# ATmega128RFA1-DevBoard-unplaced.net
KiCad netlist of a schematic drawn in EAGLE
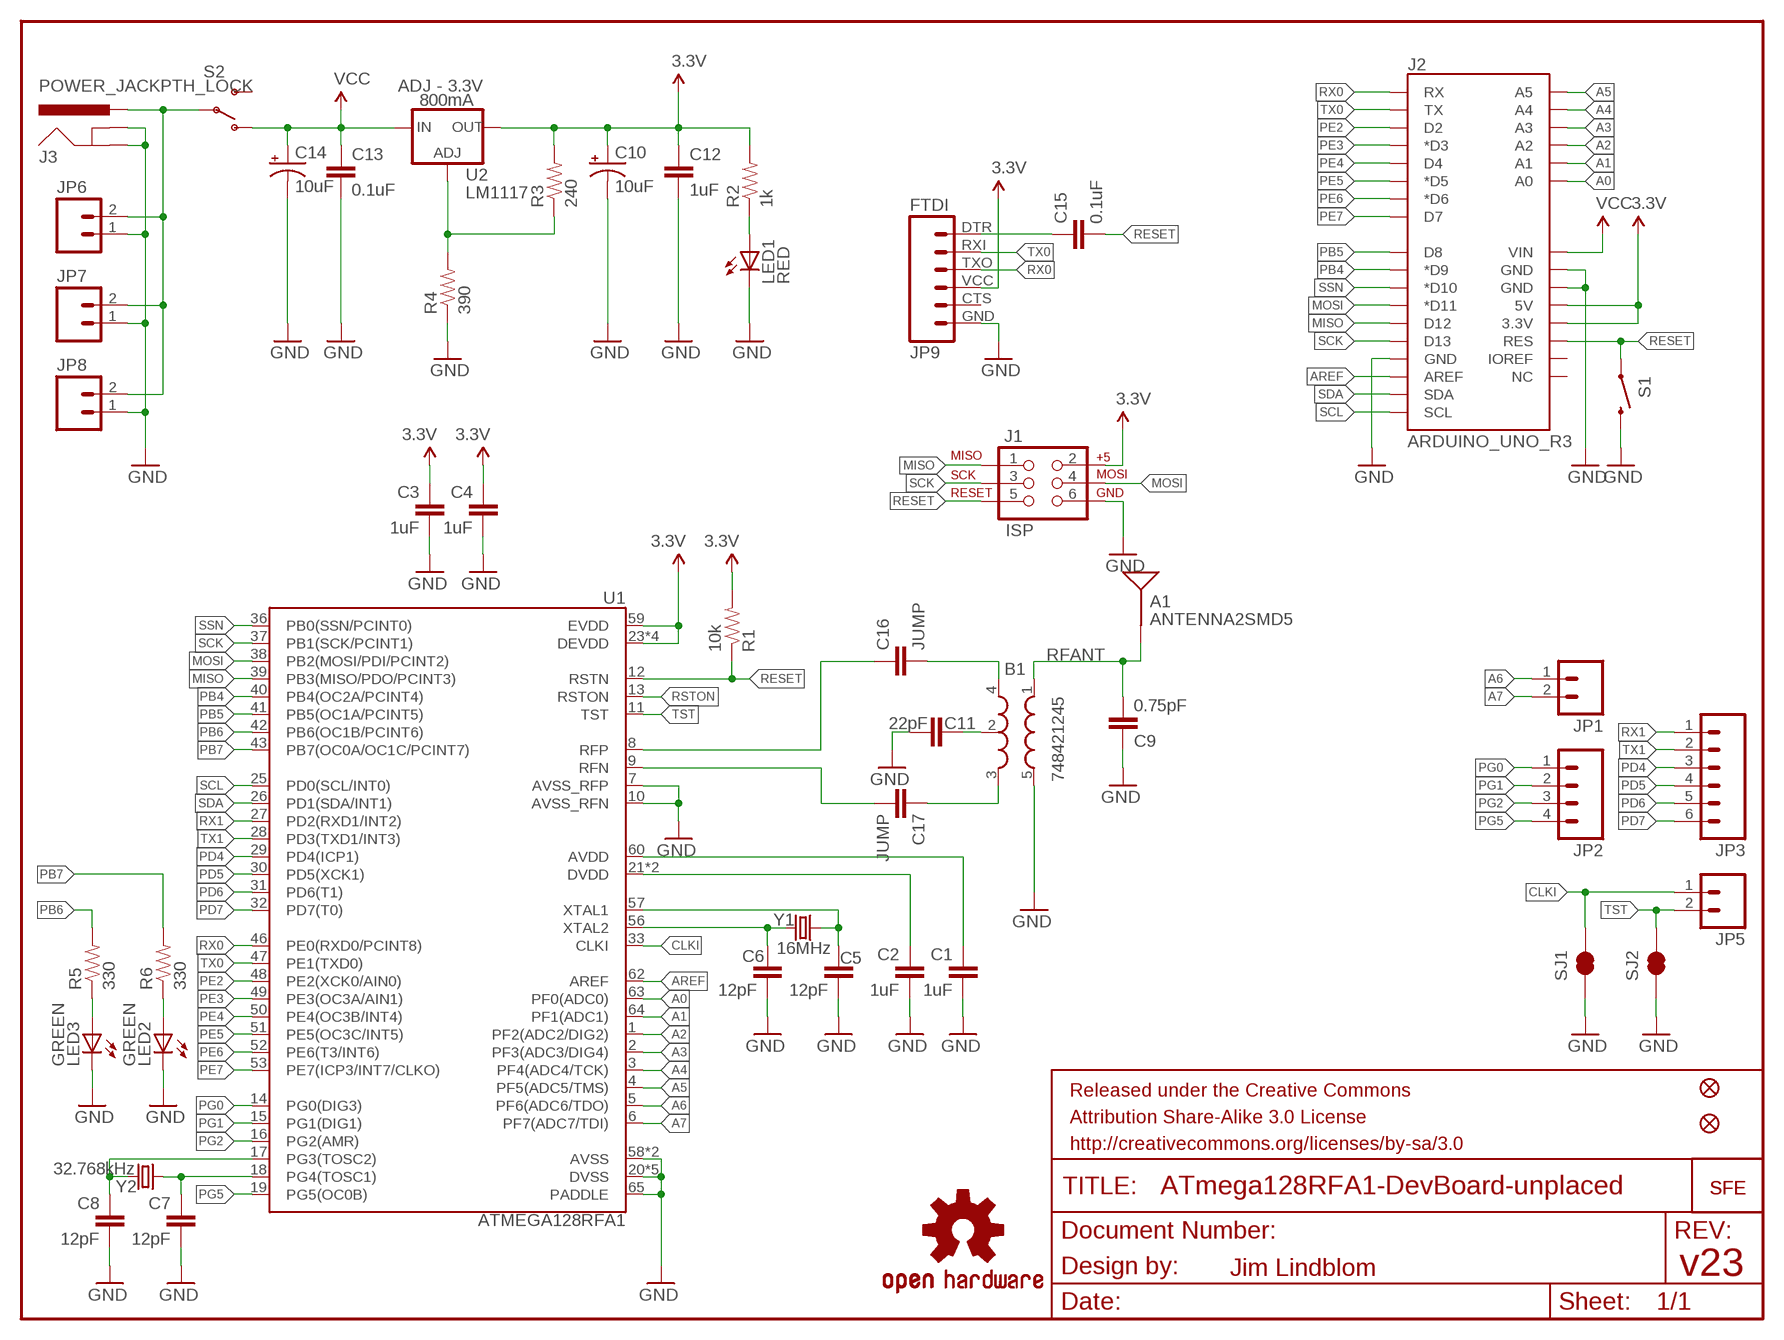
[diagram p0: schematic, sheet 1]

(export (version "E")
  (design (tool "Eeschema 10.0.6"))
  (components
    (comp (ref "A1")
      (value "ANTENNA2SMD5")
      (footprint "eagle-import:ANTENNA-CHIP5")
      (libsource (lib "eagle-import") (part "ANTENNA2SMD5"))
    )
    (comp (ref "B1")
      (value "748421245")
      (footprint "eagle-import:BALUN")
      (libsource (lib "eagle-import") (part "BALUN0805"))
    )
    (comp (ref "C1")
      (value "1uF")
      (footprint "eagle-import:0402-CAP")
      (libsource (lib "eagle-import") (part "SparkFun-Passives_CAP0402-CAP"))
    )
    (comp (ref "C2")
      (value "1uF")
      (footprint "eagle-import:0402-CAP")
      (libsource (lib "eagle-import") (part "SparkFun-Passives_CAP0402-CAP"))
    )
    (comp (ref "C3")
      (value "1uF")
      (footprint "eagle-import:0402-CAP")
      (libsource (lib "eagle-import") (part "SparkFun-Passives_CAP0402-CAP"))
    )
    (comp (ref "C4")
      (value "1uF")
      (footprint "eagle-import:0402-CAP")
      (libsource (lib "eagle-import") (part "SparkFun-Passives_CAP0402-CAP"))
    )
    (comp (ref "C5")
      (value "12pF")
      (footprint "eagle-import:0402-CAP")
      (libsource (lib "eagle-import") (part "SparkFun-Passives_CAP0402-CAP"))
    )
    (comp (ref "C6")
      (value "12pF")
      (footprint "eagle-import:0402-CAP")
      (libsource (lib "eagle-import") (part "SparkFun-Passives_CAP0402-CAP"))
    )
    (comp (ref "C7")
      (value "12pF")
      (footprint "eagle-import:0402-CAP")
      (libsource (lib "eagle-import") (part "SparkFun-Passives_CAP0402-CAP"))
    )
    (comp (ref "C8")
      (value "12pF")
      (footprint "eagle-import:0402-CAP")
      (libsource (lib "eagle-import") (part "SparkFun-Passives_CAP0402-CAP"))
    )
    (comp (ref "C9")
      (value "0.75pF")
      (footprint "eagle-import:0402-CAP")
      (libsource (lib "eagle-import") (part "SparkFun-Passives_CAP0402-CAP"))
    )
    (comp (ref "C10")
      (value "10uF")
      (footprint "eagle-import:EIA3216")
      (libsource (lib "eagle-import") (part "CAP_POL1206"))
    )
    (comp (ref "C11")
      (value "22pF")
      (footprint "eagle-import:0402-CAP")
      (libsource (lib "eagle-import") (part "SparkFun-Passives_CAP0402-CAP"))
    )
    (comp (ref "C12")
      (value "1uF")
      (footprint "eagle-import:0402-CAP")
      (libsource (lib "eagle-import") (part "SparkFun-Passives_CAP0402-CAP"))
    )
    (comp (ref "C13")
      (value "0.1uF")
      (footprint "eagle-import:0402-CAP")
      (libsource (lib "eagle-import") (part "SparkFun-Passives_CAP0402-CAP"))
    )
    (comp (ref "C14")
      (value "10uF")
      (footprint "eagle-import:EIA3216")
      (libsource (lib "eagle-import") (part "CAP_POL1206"))
    )
    (comp (ref "C15")
      (value "0.1uF")
      (footprint "eagle-import:0402-CAP")
      (libsource (lib "eagle-import") (part "SparkFun-Passives_CAP0402-CAP"))
    )
    (comp (ref "C16")
      (value "JUMP")
      (footprint "eagle-import:0402-CAP")
      (libsource (lib "eagle-import") (part "CAP0402-CAP"))
    )
    (comp (ref "C17")
      (value "JUMP")
      (footprint "eagle-import:0402-CAP")
      (libsource (lib "eagle-import") (part "CAP0402-CAP"))
    )
    (comp (ref "FID1")
      (value "FIDUCIALUFIDUCIAL")
      (footprint "eagle-import:MICRO-FIDUCIAL")
      (libsource (lib "eagle-import") (part "FIDUCIALUFIDUCIAL"))
    )
    (comp (ref "FID2")
      (value "FIDUCIALUFIDUCIAL")
      (footprint "eagle-import:MICRO-FIDUCIAL")
      (libsource (lib "eagle-import") (part "FIDUCIALUFIDUCIAL"))
    )
    (comp (ref "J1")
      (value "ISP")
      (footprint "eagle-import:2X3-NS")
      (libsource (lib "eagle-import") (part "AVR_SPI_PRG_6NS"))
    )
    (comp (ref "J2")
      (value "ARDUINO_UNO_R3")
      (footprint "eagle-import:ARDUINO_UNO_R3")
      (libsource (lib "eagle-import") (part "ARDUINO_UNO_R3"))
    )
    (comp (ref "J3")
      (value "POWER_JACKPTH_LOCK")
      (footprint "eagle-import:POWER_JACK_PTH_LOCK")
      (libsource (lib "eagle-import") (part "POWER_JACKPTH_LOCK"))
    )
    (comp (ref "JP1")
      (value "M021X02_NO_SILK")
      (footprint "eagle-import:1X02_NO_SILK")
      (libsource (lib "eagle-import") (part "M021X02_NO_SILK"))
    )
    (comp (ref "JP2")
      (value "M041X04_NO_SILK")
      (footprint "eagle-import:1X04_NO_SILK")
      (libsource (lib "eagle-import") (part "M041X04_NO_SILK"))
    )
    (comp (ref "JP3")
      (value "M06SIP-NS")
      (footprint "eagle-import:1X06_NS")
      (libsource (lib "eagle-import") (part "M06SIP-NS"))
    )
    (comp (ref "JP4")
      (value "LOGO-SFENEW")
      (footprint "eagle-import:SFE-NEW-WEBLOGO")
      (libsource (lib "eagle-import") (part "LOGO-SFENEW"))
    )
    (comp (ref "JP5")
      (value "M021X02_NO_SILK")
      (footprint "eagle-import:1X02_NO_SILK")
      (libsource (lib "eagle-import") (part "M021X02_NO_SILK"))
    )
    (comp (ref "JP6")
      (value "M02JST-PTH-2")
      (footprint "eagle-import:JST-2-PTH")
      (libsource (lib "eagle-import") (part "M02JST-PTH-2"))
    )
    (comp (ref "JP7")
      (value "M021X02_NO_SILK")
      (footprint "eagle-import:1X02_NO_SILK")
      (libsource (lib "eagle-import") (part "M021X02_NO_SILK"))
    )
    (comp (ref "JP8")
      (value "M023.5MM-NO_SILK")
      (footprint "eagle-import:SCREWTERMINAL-3.5MM-2-NS")
      (libsource (lib "eagle-import") (part "M023.5MM-NO_SILK"))
    )
    (comp (ref "JP9")
      (value "FTDI")
      (footprint "eagle-import:FTDI_BASIC")
      (libsource (lib "eagle-import") (part "FTDI_BASICPTH"))
    )
    (comp (ref "JP10")
      (value "LOGO-SFENEW")
      (footprint "eagle-import:SFE-NEW-WEBLOGO")
      (libsource (lib "eagle-import") (part "LOGO-SFENEW"))
    )
    (comp (ref "LED1")
      (value "RED")
      (footprint "eagle-import:LED-0603")
      (libsource (lib "eagle-import") (part "LED0603"))
    )
    (comp (ref "LED2")
      (value "GREEN")
      (footprint "eagle-import:LED-0603")
      (libsource (lib "eagle-import") (part "LED0603"))
    )
    (comp (ref "LED3")
      (value "GREEN")
      (footprint "eagle-import:LED-0603")
      (libsource (lib "eagle-import") (part "LED0603"))
    )
    (comp (ref "R1")
      (value "10k")
      (footprint "eagle-import:0402-RES")
      (libsource (lib "eagle-import") (part "SparkFun-Passives_RESISTOR0402-RES"))
    )
    (comp (ref "R2")
      (value "1k")
      (footprint "eagle-import:0402-RES")
      (libsource (lib "eagle-import") (part "SparkFun-Passives_RESISTOR0402-RES"))
    )
    (comp (ref "R3")
      (value "240")
      (footprint "eagle-import:0402-RES")
      (libsource (lib "eagle-import") (part "RESISTOR0402-RES"))
    )
    (comp (ref "R4")
      (value "390")
      (footprint "eagle-import:0402-RES")
      (libsource (lib "eagle-import") (part "RESISTOR0402-RES"))
    )
    (comp (ref "R5")
      (value "330")
      (footprint "eagle-import:0402-RES")
      (libsource (lib "eagle-import") (part "RESISTOR0402-RES"))
    )
    (comp (ref "R6")
      (value "330")
      (footprint "eagle-import:0402-RES")
      (libsource (lib "eagle-import") (part "RESISTOR0402-RES"))
    )
    (comp (ref "S1")
      (value "SWITCH-MOMENTARY-2SMD")
      (footprint "eagle-import:TACTILE_SWITCH_SMD")
      (libsource (lib "eagle-import") (part "SWITCH-MOMENTARY-2SMD"))
    )
    (comp (ref "S2")
      (value "SWITCH-SPST-SMD-A")
      (footprint "eagle-import:SWITCH-SPST-SMD-A")
      (libsource (lib "eagle-import") (part "SWITCH-SPST-SMD-A"))
    )
    (comp (ref "SJ1")
      (value "SOLDERJUMPERTRACE")
      (footprint "eagle-import:SJ_2S-TRACE")
      (libsource (lib "eagle-import") (part "SOLDERJUMPERTRACE"))
    )
    (comp (ref "SJ2")
      (value "SOLDERJUMPERTRACE")
      (footprint "eagle-import:SJ_2S-TRACE")
      (libsource (lib "eagle-import") (part "SOLDERJUMPERTRACE"))
    )
    (comp (ref "U$1")
      (value "OSHW-LOGOS")
      (footprint "eagle-import:OSHW-LOGO-S")
      (libsource (lib "eagle-import") (part "OSHW-LOGOS"))
    )
    (comp (ref "U1")
      (value "ATMEGA128RFA1")
      (footprint "eagle-import:QFN-64")
      (libsource (lib "eagle-import") (part "ATMEGA128RFA1"))
    )
    (comp (ref "U2")
      (value "LM1117")
      (footprint "eagle-import:SOT223")
      (libsource (lib "eagle-import") (part "V_REG_317SMD"))
    )
    (comp (ref "Y1")
      (value "16MHz")
      (footprint "eagle-import:CRYSTAL-SMD-5X3")
      (libsource (lib "eagle-import") (part "CRYSTAL5X3"))
    )
    (comp (ref "Y2")
      (value "32.768kHz")
      (footprint "eagle-import:CRYSTAL-32KHZ-SMD")
      (libsource (lib "eagle-import") (part "CRYSTAL32-SMD"))
    )
  )
  (nets
    (net (code "1") (name "/RFANT") (class "Default")
      (node (ref "A1") (pin "FEED") (pinfunction "SIGNAL_FEED") (pintype "bidirectional"))
      (node (ref "B1") (pin "1") (pinfunction "IN_1") (pintype "bidirectional"))
      (node (ref "C9") (pin "2") (pinfunction "2_2") (pintype "passive"))
    )
    (net (code "2") (name "3.3V") (class "Default")
      (node (ref "C10") (pin "A") (pinfunction "+_A") (pintype "passive"))
      (node (ref "C12") (pin "1") (pinfunction "1_1") (pintype "passive"))
      (node (ref "C3") (pin "1") (pinfunction "1_1") (pintype "passive"))
      (node (ref "C4") (pin "1") (pinfunction "1_1") (pintype "passive"))
      (node (ref "J1") (pin "2") (pinfunction "2_2") (pintype "passive"))
      (node (ref "J2") (pin "3.3V") (pinfunction "3.3V_3.3V") (pintype "bidirectional"))
      (node (ref "J2") (pin "5V") (pinfunction "5V_5V") (pintype "bidirectional"))
      (node (ref "JP9") (pin "VCC") (pinfunction "4_VCC") (pintype "passive"))
      (node (ref "R1") (pin "2") (pinfunction "2_2") (pintype "passive"))
      (node (ref "R2") (pin "2") (pinfunction "2_2") (pintype "passive"))
      (node (ref "R3") (pin "2") (pinfunction "2_2") (pintype "passive"))
      (node (ref "U1") (pin "23") (pinfunction "DEVDD_23") (pintype "bidirectional"))
      (node (ref "U1") (pin "34") (pinfunction "DEVDD_34") (pintype "bidirectional"))
      (node (ref "U1") (pin "44") (pinfunction "DEVDD_44") (pintype "bidirectional"))
      (node (ref "U1") (pin "54") (pinfunction "DEVDD_54") (pintype "bidirectional"))
      (node (ref "U1") (pin "59") (pinfunction "EVDD_59") (pintype "bidirectional"))
      (node (ref "U2") (pin "2") (pinfunction "OUT_2") (pintype "output"))
    )
    (net (code "3") (name "A0") (class "Default")
      (node (ref "J2") (pin "A0") (pinfunction "A0_A0") (pintype "bidirectional"))
      (node (ref "U1") (pin "63") (pinfunction "PF0(ADC0)_63") (pintype "bidirectional"))
    )
    (net (code "4") (name "A1") (class "Default")
      (node (ref "J2") (pin "A1") (pinfunction "A1_A1") (pintype "bidirectional"))
      (node (ref "U1") (pin "64") (pinfunction "PF1(ADC1)_64") (pintype "bidirectional"))
    )
    (net (code "5") (name "A2") (class "Default")
      (node (ref "J2") (pin "A2") (pinfunction "A2_A2") (pintype "bidirectional"))
      (node (ref "U1") (pin "1") (pinfunction "PF2(ADC2/DIG2)_1") (pintype "bidirectional"))
    )
    (net (code "6") (name "A3") (class "Default")
      (node (ref "J2") (pin "A3") (pinfunction "A3_A3") (pintype "bidirectional"))
      (node (ref "U1") (pin "2") (pinfunction "PF3(ADC3/DIG4)_2") (pintype "bidirectional"))
    )
    (net (code "7") (name "A4") (class "Default")
      (node (ref "J2") (pin "A4") (pinfunction "A4_A4") (pintype "bidirectional"))
      (node (ref "U1") (pin "3") (pinfunction "PF4(ADC4/TCK)_3") (pintype "bidirectional"))
    )
    (net (code "8") (name "A5") (class "Default")
      (node (ref "J2") (pin "A5") (pinfunction "A5_A5") (pintype "bidirectional"))
      (node (ref "U1") (pin "4") (pinfunction "PF5(ADC5/TMS)_4") (pintype "bidirectional"))
    )
    (net (code "9") (name "A6") (class "Default")
      (node (ref "JP1") (pin "1") (pinfunction "1_1") (pintype "passive"))
      (node (ref "U1") (pin "5") (pinfunction "PF6(ADC6/TDO)_5") (pintype "bidirectional"))
    )
    (net (code "10") (name "A7") (class "Default")
      (node (ref "JP1") (pin "2") (pinfunction "2_2") (pintype "passive"))
      (node (ref "U1") (pin "6") (pinfunction "PF7(ADC7/TDI)_6") (pintype "bidirectional"))
    )
    (net (code "11") (name "AREF") (class "Default")
      (node (ref "J2") (pin "AREF") (pinfunction "AREF_AREF") (pintype "bidirectional"))
      (node (ref "U1") (pin "62") (pinfunction "AREF_62") (pintype "bidirectional"))
    )
    (net (code "12") (name "CLKI") (class "Default")
      (node (ref "JP5") (pin "1") (pinfunction "1_1") (pintype "passive"))
      (node (ref "SJ1") (pin "2") (pinfunction "2_2") (pintype "passive"))
      (node (ref "U1") (pin "33") (pinfunction "CLKI_33") (pintype "bidirectional"))
    )
    (net (code "13") (name "GND") (class "Default")
      (node (ref "B1") (pin "5") (pinfunction "GND_5") (pintype "bidirectional"))
      (node (ref "C1") (pin "2") (pinfunction "2_2") (pintype "passive"))
      (node (ref "C10") (pin "C") (pinfunction "-_C") (pintype "passive"))
      (node (ref "C11") (pin "2") (pinfunction "2_2") (pintype "passive"))
      (node (ref "C12") (pin "2") (pinfunction "2_2") (pintype "passive"))
      (node (ref "C13") (pin "2") (pinfunction "2_2") (pintype "passive"))
      (node (ref "C14") (pin "C") (pinfunction "-_C") (pintype "passive"))
      (node (ref "C2") (pin "2") (pinfunction "2_2") (pintype "passive"))
      (node (ref "C3") (pin "2") (pinfunction "2_2") (pintype "passive"))
      (node (ref "C4") (pin "2") (pinfunction "2_2") (pintype "passive"))
      (node (ref "C5") (pin "2") (pinfunction "2_2") (pintype "passive"))
      (node (ref "C6") (pin "2") (pinfunction "2_2") (pintype "passive"))
      (node (ref "C7") (pin "2") (pinfunction "2_2") (pintype "passive"))
      (node (ref "C8") (pin "2") (pinfunction "2_2") (pintype "passive"))
      (node (ref "C9") (pin "1") (pinfunction "1_1") (pintype "passive"))
      (node (ref "J1") (pin "6") (pinfunction "6_6") (pintype "passive"))
      (node (ref "J2") (pin "GND@0") (pinfunction "GND_GND@0") (pintype "bidirectional"))
      (node (ref "J2") (pin "GND@1") (pinfunction "GND_GND@1") (pintype "bidirectional"))
      (node (ref "J2") (pin "GND@2") (pinfunction "GND_GND@2") (pintype "bidirectional"))
      (node (ref "J3") (pin "GND") (pinfunction "GND_GND") (pintype "bidirectional"))
      (node (ref "J3") (pin "GNDBREAK") (pinfunction "GNDBREAK_GNDBREAK") (pintype "bidirectional"))
      (node (ref "JP6") (pin "1") (pinfunction "1_1") (pintype "passive"))
      (node (ref "JP7") (pin "1") (pinfunction "1_1") (pintype "passive"))
      (node (ref "JP8") (pin "1") (pinfunction "1_1") (pintype "passive"))
      (node (ref "JP9") (pin "GND") (pinfunction "6_GND") (pintype "passive"))
      (node (ref "LED1") (pin "C") (pinfunction "C_C") (pintype "passive"))
      (node (ref "LED2") (pin "C") (pinfunction "C_C") (pintype "passive"))
      (node (ref "LED3") (pin "C") (pinfunction "C_C") (pintype "passive"))
      (node (ref "R4") (pin "1") (pinfunction "1_1") (pintype "passive"))
      (node (ref "S1") (pin "3") (pinfunction "2_3") (pintype "passive"))
      (node (ref "SJ1") (pin "1") (pinfunction "1_1") (pintype "passive"))
      (node (ref "SJ2") (pin "1") (pinfunction "1_1") (pintype "passive"))
      (node (ref "U1") (pin "10") (pinfunction "AVSS_RFN_10") (pintype "bidirectional"))
      (node (ref "U1") (pin "20") (pinfunction "DVSS_20") (pintype "bidirectional"))
      (node (ref "U1") (pin "24") (pinfunction "DVSS_24") (pintype "bidirectional"))
      (node (ref "U1") (pin "35") (pinfunction "DVSS_35") (pintype "bidirectional"))
      (node (ref "U1") (pin "45") (pinfunction "DVSS_45") (pintype "bidirectional"))
      (node (ref "U1") (pin "55") (pinfunction "DVSS_55") (pintype "bidirectional"))
      (node (ref "U1") (pin "58") (pinfunction "AVSS_58") (pintype "bidirectional"))
      (node (ref "U1") (pin "61") (pinfunction "AVSS_61") (pintype "bidirectional"))
      (node (ref "U1") (pin "65") (pinfunction "PADDLE_65") (pintype "bidirectional"))
      (node (ref "U1") (pin "7") (pinfunction "AVSS_RFP_7") (pintype "bidirectional"))
    )
    (net (code "14") (name "MISO") (class "Default")
      (node (ref "J1") (pin "1") (pinfunction "1_1") (pintype "passive"))
      (node (ref "J2") (pin "D12") (pinfunction "D12_D12") (pintype "bidirectional"))
      (node (ref "U1") (pin "39") (pinfunction "PB3(MISO/PDO/PCINT3)_39") (pintype "bidirectional"))
    )
    (net (code "15") (name "MOSI") (class "Default")
      (node (ref "J1") (pin "4") (pinfunction "4_4") (pintype "passive"))
      (node (ref "J2") (pin "D11") (pinfunction "*D11_D11") (pintype "bidirectional"))
      (node (ref "U1") (pin "38") (pinfunction "PB2(MOSI/PDI/PCINT2)_38") (pintype "bidirectional"))
    )
    (net (code "16") (name "Net-(B1-GND-Pad2)") (class "Default")
      (node (ref "B1") (pin "2") (pinfunction "GND_2") (pintype "bidirectional"))
      (node (ref "C11") (pin "1") (pinfunction "1_1") (pintype "passive"))
    )
    (net (code "17") (name "Net-(B1-OUT1)") (class "Default")
      (node (ref "B1") (pin "4") (pinfunction "OUT1_4") (pintype "bidirectional"))
      (node (ref "C16") (pin "2") (pinfunction "2_2") (pintype "passive"))
    )
    (net (code "18") (name "Net-(B1-OUT2)") (class "Default")
      (node (ref "B1") (pin "3") (pinfunction "OUT2_3") (pintype "bidirectional"))
      (node (ref "C17") (pin "1") (pinfunction "1_1") (pintype "passive"))
    )
    (net (code "19") (name "Net-(C2-Pad1)") (class "Default")
      (node (ref "C2") (pin "1") (pinfunction "1_1") (pintype "passive"))
      (node (ref "U1") (pin "21") (pinfunction "DVDD_21") (pintype "bidirectional"))
      (node (ref "U1") (pin "22") (pinfunction "DVDD_22") (pintype "bidirectional"))
    )
    (net (code "20") (name "Net-(JP9-1)") (class "Default")
      (node (ref "C15") (pin "1") (pinfunction "1_1") (pintype "passive"))
      (node (ref "JP9") (pin "DTR") (pinfunction "1_DTR") (pintype "passive"))
    )
    (net (code "21") (name "Net-(LED1-PadA)") (class "Default")
      (node (ref "LED1") (pin "A") (pinfunction "A_A") (pintype "passive"))
      (node (ref "R2") (pin "1") (pinfunction "1_1") (pintype "passive"))
    )
    (net (code "22") (name "Net-(LED2-PadA)") (class "Default")
      (node (ref "LED2") (pin "A") (pinfunction "A_A") (pintype "passive"))
      (node (ref "R6") (pin "1") (pinfunction "1_1") (pintype "passive"))
    )
    (net (code "23") (name "Net-(LED3-PadA)") (class "Default")
      (node (ref "LED3") (pin "A") (pinfunction "A_A") (pintype "passive"))
      (node (ref "R5") (pin "1") (pinfunction "1_1") (pintype "passive"))
    )
    (net (code "24") (name "Net-(S2-P)") (class "Default")
      (node (ref "J3") (pin "PWR") (pinfunction "PWR_PWR") (pintype "bidirectional"))
      (node (ref "JP6") (pin "2") (pinfunction "2_2") (pintype "passive"))
      (node (ref "JP7") (pin "2") (pinfunction "2_2") (pintype "passive"))
      (node (ref "JP8") (pin "2") (pinfunction "2_2") (pintype "passive"))
      (node (ref "S2") (pin "2") (pinfunction "P_2") (pintype "passive"))
    )
    (net (code "25") (name "Net-(U1-AVDD)") (class "Default")
      (node (ref "C1") (pin "1") (pinfunction "1_1") (pintype "passive"))
      (node (ref "U1") (pin "60") (pinfunction "AVDD_60") (pintype "bidirectional"))
    )
    (net (code "26") (name "Net-(U1-PG3(TOSC2))") (class "Default")
      (node (ref "C8") (pin "1") (pinfunction "1_1") (pintype "passive"))
      (node (ref "U1") (pin "17") (pinfunction "PG3(TOSC2)_17") (pintype "bidirectional"))
      (node (ref "Y2") (pin "X2") (pinfunction "2_X2") (pintype "passive"))
    )
    (net (code "27") (name "Net-(U1-PG4(TOSC1))") (class "Default")
      (node (ref "C7") (pin "1") (pinfunction "1_1") (pintype "passive"))
      (node (ref "U1") (pin "18") (pinfunction "PG4(TOSC1)_18") (pintype "bidirectional"))
      (node (ref "Y2") (pin "X1") (pinfunction "1_X1") (pintype "passive"))
    )
    (net (code "28") (name "Net-(U1-RFN)") (class "Default")
      (node (ref "C17") (pin "2") (pinfunction "2_2") (pintype "passive"))
      (node (ref "U1") (pin "9") (pinfunction "RFN_9") (pintype "bidirectional"))
    )
    (net (code "29") (name "Net-(U1-RFP)") (class "Default")
      (node (ref "C16") (pin "1") (pinfunction "1_1") (pintype "passive"))
      (node (ref "U1") (pin "8") (pinfunction "RFP_8") (pintype "bidirectional"))
    )
    (net (code "30") (name "Net-(U1-XTAL1)") (class "Default")
      (node (ref "C5") (pin "1") (pinfunction "1_1") (pintype "passive"))
      (node (ref "U1") (pin "57") (pinfunction "XTAL1_57") (pintype "bidirectional"))
      (node (ref "Y1") (pin "3") (pinfunction "2_3") (pintype "passive"))
    )
    (net (code "31") (name "Net-(U1-XTAL2)") (class "Default")
      (node (ref "C6") (pin "1") (pinfunction "1_1") (pintype "passive"))
      (node (ref "U1") (pin "56") (pinfunction "XTAL2_56") (pintype "bidirectional"))
      (node (ref "Y1") (pin "1") (pinfunction "1_1") (pintype "passive"))
    )
    (net (code "32") (name "Net-(U2-ADJ)") (class "Default")
      (node (ref "R3") (pin "1") (pinfunction "1_1") (pintype "passive"))
      (node (ref "R4") (pin "2") (pinfunction "2_2") (pintype "passive"))
      (node (ref "U2") (pin "1") (pinfunction "ADJ_1") (pintype "input"))
    )
    (net (code "33") (name "PB4") (class "Default")
      (node (ref "J2") (pin "D9") (pinfunction "*D9_D9") (pintype "bidirectional"))
      (node (ref "U1") (pin "40") (pinfunction "PB4(OC2A/PCINT4)_40") (pintype "bidirectional"))
    )
    (net (code "34") (name "PB5") (class "Default")
      (node (ref "J2") (pin "D8") (pinfunction "D8_D8") (pintype "bidirectional"))
      (node (ref "U1") (pin "41") (pinfunction "PB5(OC1A/PCINT5)_41") (pintype "bidirectional"))
    )
    (net (code "35") (name "PB6") (class "Default")
      (node (ref "R5") (pin "2") (pinfunction "2_2") (pintype "passive"))
      (node (ref "U1") (pin "42") (pinfunction "PB6(OC1B/PCINT6)_42") (pintype "bidirectional"))
    )
    (net (code "36") (name "PB7") (class "Default")
      (node (ref "R6") (pin "2") (pinfunction "2_2") (pintype "passive"))
      (node (ref "U1") (pin "43") (pinfunction "PB7(OC0A/OC1C/PCINT7)_43") (pintype "bidirectional"))
    )
    (net (code "37") (name "PD4") (class "Default")
      (node (ref "JP3") (pin "3") (pinfunction "3_3") (pintype "passive"))
      (node (ref "U1") (pin "29") (pinfunction "PD4(ICP1)_29") (pintype "bidirectional"))
    )
    (net (code "38") (name "PD5") (class "Default")
      (node (ref "JP3") (pin "4") (pinfunction "4_4") (pintype "passive"))
      (node (ref "U1") (pin "30") (pinfunction "PD5(XCK1)_30") (pintype "bidirectional"))
    )
    (net (code "39") (name "PD6") (class "Default")
      (node (ref "JP3") (pin "5") (pinfunction "5_5") (pintype "passive"))
      (node (ref "U1") (pin "31") (pinfunction "PD6(T1)_31") (pintype "bidirectional"))
    )
    (net (code "40") (name "PD7") (class "Default")
      (node (ref "JP3") (pin "6") (pinfunction "6_6") (pintype "passive"))
      (node (ref "U1") (pin "32") (pinfunction "PD7(T0)_32") (pintype "bidirectional"))
    )
    (net (code "41") (name "PE2") (class "Default")
      (node (ref "J2") (pin "D2") (pinfunction "D2_D2") (pintype "bidirectional"))
      (node (ref "U1") (pin "48") (pinfunction "PE2(XCK0/AIN0)_48") (pintype "bidirectional"))
    )
    (net (code "42") (name "PE3") (class "Default")
      (node (ref "J2") (pin "D3") (pinfunction "*D3_D3") (pintype "bidirectional"))
      (node (ref "U1") (pin "49") (pinfunction "PE3(OC3A/AIN1)_49") (pintype "bidirectional"))
    )
    (net (code "43") (name "PE4") (class "Default")
      (node (ref "J2") (pin "D4") (pinfunction "D4_D4") (pintype "bidirectional"))
      (node (ref "U1") (pin "50") (pinfunction "PE4(OC3B/INT4)_50") (pintype "bidirectional"))
    )
    (net (code "44") (name "PE5") (class "Default")
      (node (ref "J2") (pin "D5") (pinfunction "*D5_D5") (pintype "bidirectional"))
      (node (ref "U1") (pin "51") (pinfunction "PE5(OC3C/INT5)_51") (pintype "bidirectional"))
    )
    (net (code "45") (name "PE6") (class "Default")
      (node (ref "J2") (pin "D6") (pinfunction "*D6_D6") (pintype "bidirectional"))
      (node (ref "U1") (pin "52") (pinfunction "PE6(T3/INT6)_52") (pintype "bidirectional"))
    )
    (net (code "46") (name "PE7") (class "Default")
      (node (ref "J2") (pin "D7") (pinfunction "D7_D7") (pintype "bidirectional"))
      (node (ref "U1") (pin "53") (pinfunction "PE7(ICP3/INT7/CLKO)_53") (pintype "bidirectional"))
    )
    (net (code "47") (name "PG0") (class "Default")
      (node (ref "JP2") (pin "1") (pinfunction "1_1") (pintype "passive"))
      (node (ref "U1") (pin "14") (pinfunction "PG0(DIG3)_14") (pintype "bidirectional"))
    )
    (net (code "48") (name "PG1") (class "Default")
      (node (ref "JP2") (pin "2") (pinfunction "2_2") (pintype "passive"))
      (node (ref "U1") (pin "15") (pinfunction "PG1(DIG1)_15") (pintype "bidirectional"))
    )
    (net (code "49") (name "PG2") (class "Default")
      (node (ref "JP2") (pin "3") (pinfunction "3_3") (pintype "passive"))
      (node (ref "U1") (pin "16") (pinfunction "PG2(AMR)_16") (pintype "bidirectional"))
    )
    (net (code "50") (name "PG5") (class "Default")
      (node (ref "JP2") (pin "4") (pinfunction "4_4") (pintype "passive"))
      (node (ref "U1") (pin "19") (pinfunction "PG5(OC0B)_19") (pintype "bidirectional"))
    )
    (net (code "51") (name "RESET") (class "Default")
      (node (ref "C15") (pin "2") (pinfunction "2_2") (pintype "passive"))
      (node (ref "J1") (pin "5") (pinfunction "5_5") (pintype "passive"))
      (node (ref "J2") (pin "RES") (pinfunction "RES_RES") (pintype "bidirectional"))
      (node (ref "R1") (pin "1") (pinfunction "1_1") (pintype "passive"))
      (node (ref "S1") (pin "1") (pinfunction "1_1") (pintype "passive"))
      (node (ref "U1") (pin "12") (pinfunction "RSTN_12") (pintype "bidirectional"))
    )
    (net (code "52") (name "RSTON") (class "Default")
      (node (ref "U1") (pin "13") (pinfunction "RSTON_13") (pintype "bidirectional"))
    )
    (net (code "53") (name "RX0") (class "Default")
      (node (ref "J2") (pin "RX") (pinfunction "RX_RX") (pintype "bidirectional"))
      (node (ref "JP9") (pin "TXO") (pinfunction "3_TXO") (pintype "passive"))
      (node (ref "U1") (pin "46") (pinfunction "PE0(RXD0/PCINT8)_46") (pintype "bidirectional"))
    )
    (net (code "54") (name "RX1") (class "Default")
      (node (ref "JP3") (pin "1") (pinfunction "1_1") (pintype "passive"))
      (node (ref "U1") (pin "27") (pinfunction "PD2(RXD1/INT2)_27") (pintype "bidirectional"))
    )
    (net (code "55") (name "SCK") (class "Default")
      (node (ref "J1") (pin "3") (pinfunction "3_3") (pintype "passive"))
      (node (ref "J2") (pin "D13") (pinfunction "D13_D13") (pintype "bidirectional"))
      (node (ref "U1") (pin "37") (pinfunction "PB1(SCK/PCINT1)_37") (pintype "bidirectional"))
    )
    (net (code "56") (name "SCL") (class "Default")
      (node (ref "J2") (pin "SCL") (pinfunction "SCL_SCL") (pintype "bidirectional"))
      (node (ref "U1") (pin "25") (pinfunction "PD0(SCL/INT0)_25") (pintype "bidirectional"))
    )
    (net (code "57") (name "SDA") (class "Default")
      (node (ref "J2") (pin "SDA") (pinfunction "SDA_SDA") (pintype "bidirectional"))
      (node (ref "U1") (pin "26") (pinfunction "PD1(SDA/INT1)_26") (pintype "bidirectional"))
    )
    (net (code "58") (name "SSN") (class "Default")
      (node (ref "J2") (pin "D10") (pinfunction "*D10_D10") (pintype "bidirectional"))
      (node (ref "U1") (pin "36") (pinfunction "PB0(SSN/PCINT0)_36") (pintype "bidirectional"))
    )
    (net (code "59") (name "TST") (class "Default")
      (node (ref "JP5") (pin "2") (pinfunction "2_2") (pintype "passive"))
      (node (ref "SJ2") (pin "2") (pinfunction "2_2") (pintype "passive"))
      (node (ref "U1") (pin "11") (pinfunction "TST_11") (pintype "bidirectional"))
    )
    (net (code "60") (name "TX0") (class "Default")
      (node (ref "J2") (pin "TX") (pinfunction "TX_TX") (pintype "bidirectional"))
      (node (ref "JP9") (pin "RXI") (pinfunction "2_RXI") (pintype "passive"))
      (node (ref "U1") (pin "47") (pinfunction "PE1(TXD0)_47") (pintype "bidirectional"))
    )
    (net (code "61") (name "TX1") (class "Default")
      (node (ref "JP3") (pin "2") (pinfunction "2_2") (pintype "passive"))
      (node (ref "U1") (pin "28") (pinfunction "PD3(TXD1/INT3)_28") (pintype "bidirectional"))
    )
    (net (code "62") (name "VCC") (class "Default")
      (node (ref "C13") (pin "1") (pinfunction "1_1") (pintype "passive"))
      (node (ref "C14") (pin "A") (pinfunction "+_A") (pintype "passive"))
      (node (ref "J2") (pin "VIN") (pinfunction "VIN_VIN") (pintype "bidirectional"))
      (node (ref "S2") (pin "1") (pinfunction "O_1") (pintype "passive"))
      (node (ref "U2") (pin "3") (pinfunction "IN_3") (pintype "input"))
    )
    (net (code "63") (name "unconnected-(J2-PadIOREF)") (class "Default")
      (node (ref "J2") (pin "IOREF") (pinfunction "IOREF_IOREF") (pintype "bidirectional"))
    )
    (net (code "64") (name "unconnected-(J2-PadNC)") (class "Default")
      (node (ref "J2") (pin "NC") (pinfunction "NC_NC") (pintype "bidirectional"))
    )
    (net (code "65") (name "unconnected-(JP9-5-PadCTS)") (class "Default")
      (node (ref "JP9") (pin "CTS") (pinfunction "5_CTS") (pintype "passive"))
    )
    (net (code "66") (name "unconnected-(S2-S-Pad3)") (class "Default")
      (node (ref "S2") (pin "3") (pinfunction "S_3") (pintype "passive"))
    )
  )
)
